# PSU.net
KiCad netlist of a schematic drawn in EAGLE
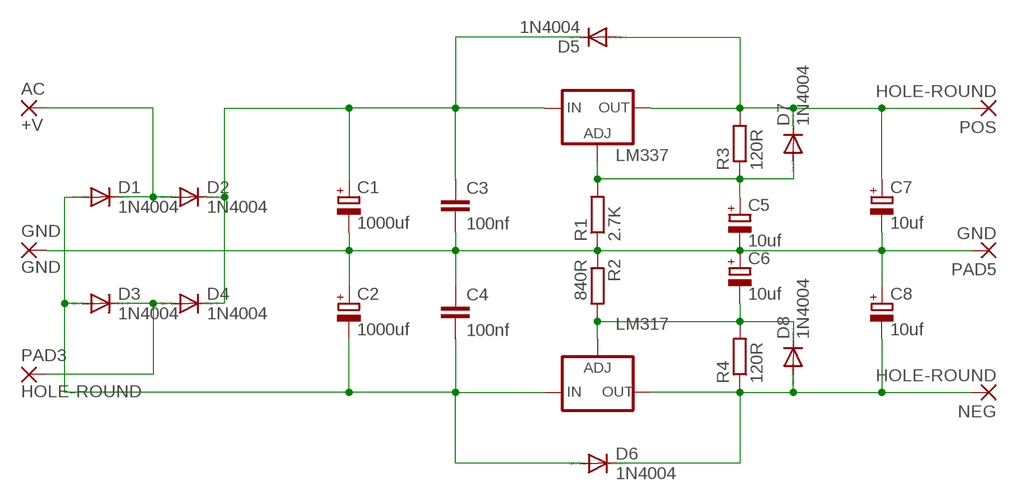
[diagram p0: schematic, sheet 1]

(export (version "E")
  (design (tool "Eeschema 10.0.6"))
  (components
    (comp (ref "AC")
      (value "+V")
      (footprint "eagle-import:HOLE-ROUND")
      (libsource (lib "eagle-import") (part "HOLE-ROUND"))
    )
    (comp (ref "C1")
      (value "1000uf")
      (footprint "eagle-import:E3,5-10")
      (libsource (lib "eagle-import") (part "CPOL-EUE3.5-10"))
    )
    (comp (ref "C2")
      (value "1000uf")
      (footprint "eagle-import:E3,5-10")
      (libsource (lib "eagle-import") (part "CPOL-EUE3.5-10"))
    )
    (comp (ref "C3")
      (value "100nf")
      (footprint "eagle-import:C025-025X050")
      (libsource (lib "eagle-import") (part "C-EU025-025X050"))
    )
    (comp (ref "C4")
      (value "100nf")
      (footprint "eagle-import:C025-025X050")
      (libsource (lib "eagle-import") (part "C-EU025-025X050"))
    )
    (comp (ref "C5")
      (value "10uf")
      (footprint "eagle-import:E2,5-5")
      (libsource (lib "eagle-import") (part "CPOL-EUE2.5-5"))
    )
    (comp (ref "C6")
      (value "10uf")
      (footprint "eagle-import:E2,5-5")
      (libsource (lib "eagle-import") (part "CPOL-EUE2.5-5"))
    )
    (comp (ref "C7")
      (value "10uf")
      (footprint "eagle-import:E2,5-5")
      (libsource (lib "eagle-import") (part "CPOL-EUE2.5-5"))
    )
    (comp (ref "C8")
      (value "10uf")
      (footprint "eagle-import:E2,5-5")
      (libsource (lib "eagle-import") (part "CPOL-EUE2.5-5"))
    )
    (comp (ref "D1")
      (value "1N4004")
      (footprint "eagle-import:DO41-10")
      (libsource (lib "eagle-import") (part "1N4004"))
    )
    (comp (ref "D2")
      (value "1N4004")
      (footprint "eagle-import:DO41-10")
      (libsource (lib "eagle-import") (part "1N4004"))
    )
    (comp (ref "D3")
      (value "1N4004")
      (footprint "eagle-import:DO41-10")
      (libsource (lib "eagle-import") (part "1N4004"))
    )
    (comp (ref "D4")
      (value "1N4004")
      (footprint "eagle-import:DO41-10")
      (libsource (lib "eagle-import") (part "1N4004"))
    )
    (comp (ref "D5")
      (value "1N4004")
      (footprint "eagle-import:DO41-10")
      (libsource (lib "eagle-import") (part "1N4004"))
    )
    (comp (ref "D6")
      (value "1N4004")
      (footprint "eagle-import:DO41-10")
      (libsource (lib "eagle-import") (part "1N4004"))
    )
    (comp (ref "D7")
      (value "1N4004")
      (footprint "eagle-import:DO41-10")
      (libsource (lib "eagle-import") (part "1N4004"))
    )
    (comp (ref "D8")
      (value "1N4004")
      (footprint "eagle-import:DO41-10")
      (libsource (lib "eagle-import") (part "1N4004"))
    )
    (comp (ref "GND")
      (value "GND")
      (footprint "eagle-import:HOLE-SQUARE")
      (libsource (lib "eagle-import") (part "HOLE-SQUARE"))
    )
    (comp (ref "LM317")
      (value "LM337TS")
      (footprint "eagle-import:337TS")
      (libsource (lib "eagle-import") (part "LM337TS"))
    )
    (comp (ref "LM337")
      (value "LM317TS")
      (footprint "eagle-import:317TS")
      (libsource (lib "eagle-import") (part "LM317TS"))
    )
    (comp (ref "NEG")
      (value "HOLE-ROUND")
      (footprint "eagle-import:HOLE-ROUND")
      (libsource (lib "eagle-import") (part "HOLE-ROUND"))
    )
    (comp (ref "PAD3")
      (value "HOLE-ROUND")
      (footprint "eagle-import:HOLE-ROUND")
      (libsource (lib "eagle-import") (part "HOLE-ROUND"))
    )
    (comp (ref "PAD5")
      (value "GND")
      (footprint "eagle-import:HOLE-SQUARE")
      (libsource (lib "eagle-import") (part "HOLE-SQUARE"))
    )
    (comp (ref "POS")
      (value "HOLE-ROUND")
      (footprint "eagle-import:HOLE-ROUND")
      (libsource (lib "eagle-import") (part "HOLE-ROUND"))
    )
    (comp (ref "R1")
      (value "2.7K")
      (footprint "eagle-import:0204_7")
      (libsource (lib "eagle-import") (part "R-EU_0204/7"))
    )
    (comp (ref "R2")
      (value "840R")
      (footprint "eagle-import:0204_7")
      (libsource (lib "eagle-import") (part "R-EU_0204/7"))
    )
    (comp (ref "R3")
      (value "120R")
      (footprint "eagle-import:0204_7")
      (libsource (lib "eagle-import") (part "R-EU_0204/7"))
    )
    (comp (ref "R4")
      (value "120R")
      (footprint "eagle-import:0204_7")
      (libsource (lib "eagle-import") (part "R-EU_0204/7"))
    )
  )
  (nets
    (net (code "1") (name "Net-(AC-P)") (class "Default")
      (node (ref "AC") (pin "1") (pinfunction "P_1") (pintype "passive"))
      (node (ref "D1") (pin "C") (pinfunction "C_C") (pintype "passive"))
      (node (ref "D2") (pin "A") (pinfunction "A_A") (pintype "passive"))
    )
    (net (code "2") (name "Net-(GND-P)") (class "Default")
      (node (ref "C1") (pin "-") (pinfunction "-_-") (pintype "passive"))
      (node (ref "C2") (pin "+") (pinfunction "+_+") (pintype "passive"))
      (node (ref "C3") (pin "2") (pinfunction "2_2") (pintype "passive"))
      (node (ref "C4") (pin "1") (pinfunction "1_1") (pintype "passive"))
      (node (ref "C5") (pin "-") (pinfunction "-_-") (pintype "passive"))
      (node (ref "C6") (pin "+") (pinfunction "+_+") (pintype "passive"))
      (node (ref "C7") (pin "-") (pinfunction "-_-") (pintype "passive"))
      (node (ref "C8") (pin "+") (pinfunction "+_+") (pintype "passive"))
      (node (ref "GND") (pin "1") (pinfunction "P_1") (pintype "passive"))
      (node (ref "PAD5") (pin "1") (pinfunction "P_1") (pintype "passive"))
      (node (ref "R1") (pin "1") (pinfunction "1_1") (pintype "passive"))
      (node (ref "R2") (pin "1") (pinfunction "1_1") (pintype "passive"))
    )
    (net (code "3") (name "Net-(LM317-ADJ)") (class "Default")
      (node (ref "C6") (pin "-") (pinfunction "-_-") (pintype "passive"))
      (node (ref "D8") (pin "C") (pinfunction "C_C") (pintype "passive"))
      (node (ref "LM317") (pin "1") (pinfunction "ADJ_1") (pintype "input"))
      (node (ref "R2") (pin "2") (pinfunction "2_2") (pintype "passive"))
      (node (ref "R4") (pin "2") (pinfunction "2_2") (pintype "passive"))
    )
    (net (code "4") (name "Net-(LM317-IN)") (class "Default")
      (node (ref "C2") (pin "-") (pinfunction "-_-") (pintype "passive"))
      (node (ref "C4") (pin "2") (pinfunction "2_2") (pintype "passive"))
      (node (ref "D1") (pin "A") (pinfunction "A_A") (pintype "passive"))
      (node (ref "D3") (pin "A") (pinfunction "A_A") (pintype "passive"))
      (node (ref "D6") (pin "A") (pinfunction "A_A") (pintype "passive"))
      (node (ref "LM317") (pin "2") (pinfunction "IN_2") (pintype "input"))
    )
    (net (code "5") (name "Net-(LM317-OUT)") (class "Default")
      (node (ref "C8") (pin "-") (pinfunction "-_-") (pintype "passive"))
      (node (ref "D6") (pin "C") (pinfunction "C_C") (pintype "passive"))
      (node (ref "D8") (pin "A") (pinfunction "A_A") (pintype "passive"))
      (node (ref "LM317") (pin "3") (pinfunction "OUT_3") (pintype "passive"))
      (node (ref "NEG") (pin "1") (pinfunction "P_1") (pintype "passive"))
      (node (ref "R4") (pin "1") (pinfunction "1_1") (pintype "passive"))
    )
    (net (code "6") (name "Net-(LM337-ADJ)") (class "Default")
      (node (ref "C5") (pin "+") (pinfunction "+_+") (pintype "passive"))
      (node (ref "D7") (pin "A") (pinfunction "A_A") (pintype "passive"))
      (node (ref "LM337") (pin "1") (pinfunction "ADJ_1") (pintype "input"))
      (node (ref "R1") (pin "2") (pinfunction "2_2") (pintype "passive"))
      (node (ref "R3") (pin "1") (pinfunction "1_1") (pintype "passive"))
    )
    (net (code "7") (name "Net-(LM337-IN)") (class "Default")
      (node (ref "C1") (pin "+") (pinfunction "+_+") (pintype "passive"))
      (node (ref "C3") (pin "1") (pinfunction "1_1") (pintype "passive"))
      (node (ref "D2") (pin "C") (pinfunction "C_C") (pintype "passive"))
      (node (ref "D4") (pin "C") (pinfunction "C_C") (pintype "passive"))
      (node (ref "D5") (pin "C") (pinfunction "C_C") (pintype "passive"))
      (node (ref "LM337") (pin "3") (pinfunction "IN_3") (pintype "input"))
    )
    (net (code "8") (name "Net-(LM337-OUT)") (class "Default")
      (node (ref "C7") (pin "+") (pinfunction "+_+") (pintype "passive"))
      (node (ref "D5") (pin "A") (pinfunction "A_A") (pintype "passive"))
      (node (ref "D7") (pin "C") (pinfunction "C_C") (pintype "passive"))
      (node (ref "LM337") (pin "2") (pinfunction "OUT_2") (pintype "passive"))
      (node (ref "POS") (pin "1") (pinfunction "P_1") (pintype "passive"))
      (node (ref "R3") (pin "2") (pinfunction "2_2") (pintype "passive"))
    )
    (net (code "9") (name "Net-(PAD3-P)") (class "Default")
      (node (ref "D3") (pin "C") (pinfunction "C_C") (pintype "passive"))
      (node (ref "D4") (pin "A") (pinfunction "A_A") (pintype "passive"))
      (node (ref "PAD3") (pin "1") (pinfunction "P_1") (pintype "passive"))
    )
  )
)
